# 3_-PowerIN_Page.net
KiCad netlist of a schematic drawn in Altium Designer
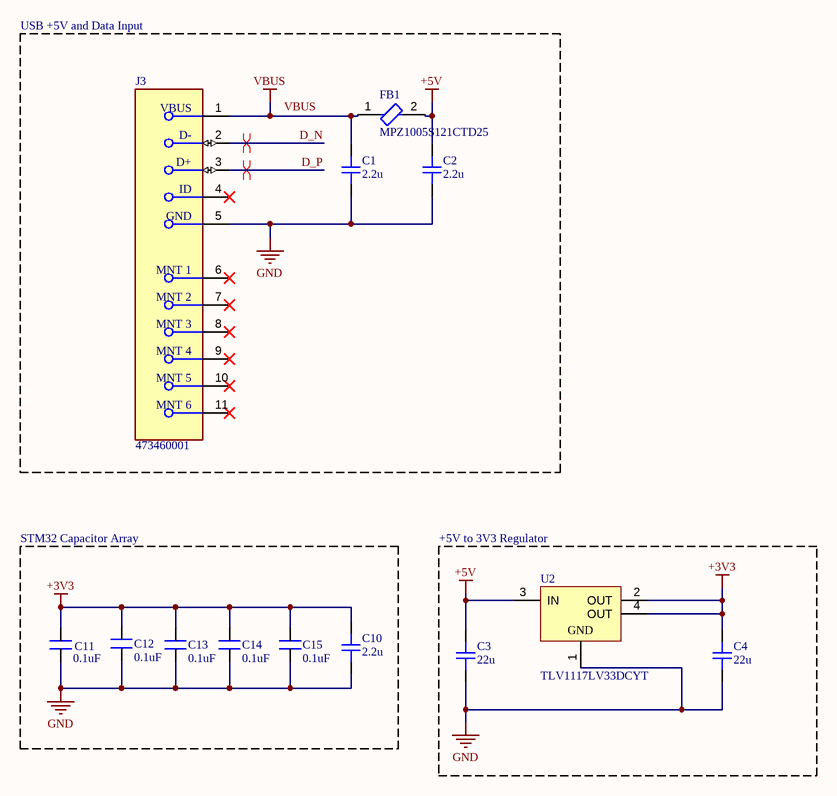
[diagram p0: [3]-PowerIN_Page.SchDoc]

(export (version "E")
  (design (tool "Eeschema 10.0.6"))
  (components
    (comp (ref "C1")
      (value "2.2u")
      (footprint "CAP_0603")
      (description "Capacitor SMD 0603")
      (libsource (lib "Schematic-Lib-PhilsLab") (part "CAP_0603"))
    )
    (comp (ref "C2")
      (value "2.2u")
      (footprint "CAP_0603")
      (description "Capacitor SMD 0603")
      (libsource (lib "Schematic-Lib-PhilsLab") (part "CAP_0603"))
    )
    (comp (ref "C3")
      (value "22u")
      (footprint "CAP_0805")
      (description "Capacitor SMD 0805")
      (libsource (lib "Schematic-Lib-PhilsLab") (part "CAP_0805"))
    )
    (comp (ref "C4")
      (value "22u")
      (footprint "CAP_0805")
      (description "Capacitor SMD 0805")
      (libsource (lib "Schematic-Lib-PhilsLab") (part "CAP_0805"))
    )
    (comp (ref "C10")
      (value "2.2u")
      (footprint "CAP_0603")
      (description "Capacitor SMD 0603")
      (libsource (lib "Schematic-Lib-PhilsLab") (part "CAP_0603"))
    )
    (comp (ref "C11")
      (value "0.1uF")
      (footprint "CAP_0805")
      (description "0.1µF ±5% 50V Ceramic Capacitor X7R 0805 (2012 Metric)")
      (fields
        (field (name "MANUFACTURER") "KEMET")
        (field (name "MANUFACTURING PART NUMBER") "C0805C104J5RACTU")
      )
      (libsource (lib "STM_SCH_LIB") (part "CAP_0.1uF-50V-5%-0805"))
    )
    (comp (ref "C12")
      (value "0.1uF")
      (footprint "CAP_0805")
      (description "0.1µF ±5% 50V Ceramic Capacitor X7R 0805 (2012 Metric)")
      (fields
        (field (name "MANUFACTURER") "KEMET")
        (field (name "MANUFACTURING PART NUMBER") "C0805C104J5RACTU")
      )
      (libsource (lib "STM_SCH_LIB") (part "CAP_0.1uF-50V-5%-0805"))
    )
    (comp (ref "C13")
      (value "0.1uF")
      (footprint "CAP_0805")
      (description "0.1µF ±5% 50V Ceramic Capacitor X7R 0805 (2012 Metric)")
      (fields
        (field (name "MANUFACTURER") "KEMET")
        (field (name "MANUFACTURING PART NUMBER") "C0805C104J5RACTU")
      )
      (libsource (lib "STM_SCH_LIB") (part "CAP_0.1uF-50V-5%-0805"))
    )
    (comp (ref "C14")
      (value "0.1uF")
      (footprint "CAP_0805")
      (description "0.1µF ±5% 50V Ceramic Capacitor X7R 0805 (2012 Metric)")
      (fields
        (field (name "MANUFACTURER") "KEMET")
        (field (name "MANUFACTURING PART NUMBER") "C0805C104J5RACTU")
      )
      (libsource (lib "STM_SCH_LIB") (part "CAP_0.1uF-50V-5%-0805"))
    )
    (comp (ref "C15")
      (value "0.1uF")
      (footprint "CAP_0805")
      (description "0.1µF ±5% 50V Ceramic Capacitor X7R 0805 (2012 Metric)")
      (fields
        (field (name "MANUFACTURER") "KEMET")
        (field (name "MANUFACTURING PART NUMBER") "C0805C104J5RACTU")
      )
      (libsource (lib "STM_SCH_LIB") (part "CAP_0.1uF-50V-5%-0805"))
    )
    (comp (ref "FB1")
      (value "MPZ1005S121CTD25")
      (footprint "FP-MPZ1005-IPC_C")
      (description "Power line Ferrite Bead 120Ω @ 100MHz 1.2A DCR 0.09Ω AEC-Q200 SMD 0402")
      (fields (field (name "TOLERANCE") "25%"))
      (libsource (lib "Altium Content Vault") (part "5f30dd21d616792df468990f7003faa"))
    )
    (comp (ref "J3")
      (value "473460001")
      (footprint "FP-473460001-MFG")
      (description "CONN RCPT USB2.0 MICRO B SMD R/A")
      (fields
        (field (name "OCTOPART") "https://octopart.com/47346-0001-molex-7164928")
        (field (name "MANUFACTURER") "Molex")
      )
      (libsource (lib "Altium Content Vault") (part "53ae1f1d9b557310b43ca686e5bb76a"))
    )
    (comp (ref "U2")
      (value "TLV1117LV33DCYT")
      (footprint "DCY0004A_M")
      (fields (field (name "MANUFACTURER") "Texas Instruments"))
      (libsource (lib "Altium Content Vault") (part "TI-TLV1117LV33DCY4"))
    )
  )
  (nets
    (net (code "1") (name "+3V3") (class "Default")
      (node (ref "C10") (pin "2") (pinfunction "2_2") (pintype "passive"))
      (node (ref "C11") (pin "2") (pinfunction "2_2") (pintype "passive"))
      (node (ref "C12") (pin "2") (pinfunction "2_2") (pintype "passive"))
      (node (ref "C13") (pin "2") (pinfunction "2_2") (pintype "passive"))
      (node (ref "C14") (pin "2") (pinfunction "2_2") (pintype "passive"))
      (node (ref "C15") (pin "2") (pinfunction "2_2") (pintype "passive"))
      (node (ref "C4") (pin "2") (pinfunction "2_2") (pintype "passive"))
      (node (ref "U2") (pin "2") (pinfunction "OUT_2") (pintype "power_in"))
      (node (ref "U2") (pin "4") (pinfunction "OUT_4") (pintype "power_in"))
    )
    (net (code "2") (name "+5V") (class "Default")
      (node (ref "C2") (pin "2") (pinfunction "2_2") (pintype "passive"))
      (node (ref "C3") (pin "2") (pinfunction "2_2") (pintype "passive"))
      (node (ref "FB1") (pin "2") (pinfunction "2_2") (pintype "passive"))
      (node (ref "U2") (pin "3") (pinfunction "IN_3") (pintype "power_in"))
    )
    (net (code "3") (name "/D_N") (class "Default")
      (node (ref "J3") (pin "2") (pinfunction "D-_2") (pintype "bidirectional"))
    )
    (net (code "4") (name "/D_P") (class "Default")
      (node (ref "J3") (pin "3") (pinfunction "D+_3") (pintype "bidirectional"))
    )
    (net (code "5") (name "GND") (class "Default")
      (node (ref "C1") (pin "1") (pinfunction "1_1") (pintype "passive"))
      (node (ref "C10") (pin "1") (pinfunction "1_1") (pintype "passive"))
      (node (ref "C11") (pin "1") (pinfunction "1_1") (pintype "passive"))
      (node (ref "C12") (pin "1") (pinfunction "1_1") (pintype "passive"))
      (node (ref "C13") (pin "1") (pinfunction "1_1") (pintype "passive"))
      (node (ref "C14") (pin "1") (pinfunction "1_1") (pintype "passive"))
      (node (ref "C15") (pin "1") (pinfunction "1_1") (pintype "passive"))
      (node (ref "C2") (pin "1") (pinfunction "1_1") (pintype "passive"))
      (node (ref "C3") (pin "1") (pinfunction "1_1") (pintype "passive"))
      (node (ref "C4") (pin "1") (pinfunction "1_1") (pintype "passive"))
      (node (ref "J3") (pin "5") (pinfunction "GND_5") (pintype "power_in"))
      (node (ref "U2") (pin "1") (pinfunction "GND_1") (pintype "power_in"))
    )
    (net (code "6") (name "VBUS") (class "Default")
      (node (ref "C1") (pin "2") (pinfunction "2_2") (pintype "passive"))
      (node (ref "FB1") (pin "1") (pinfunction "1_1") (pintype "passive"))
      (node (ref "J3") (pin "1") (pinfunction "VBUS_1") (pintype "power_in"))
    )
    (net (code "7") (name "unconnected-(J3-ID-Pad4)") (class "Default")
      (node (ref "J3") (pin "4") (pinfunction "ID_4") (pintype "passive+no_connect"))
    )
    (net (code "8") (name "unconnected-(J3-MNT_1-Pad6)") (class "Default")
      (node (ref "J3") (pin "6") (pinfunction "MNT_1_6") (pintype "passive+no_connect"))
    )
    (net (code "9") (name "unconnected-(J3-MNT_2-Pad7)") (class "Default")
      (node (ref "J3") (pin "7") (pinfunction "MNT_2_7") (pintype "passive+no_connect"))
    )
    (net (code "10") (name "unconnected-(J3-MNT_3-Pad8)") (class "Default")
      (node (ref "J3") (pin "8") (pinfunction "MNT_3_8") (pintype "passive+no_connect"))
    )
    (net (code "11") (name "unconnected-(J3-MNT_4-Pad9)") (class "Default")
      (node (ref "J3") (pin "9") (pinfunction "MNT_4_9") (pintype "passive+no_connect"))
    )
    (net (code "12") (name "unconnected-(J3-MNT_5-Pad10)") (class "Default")
      (node (ref "J3") (pin "10") (pinfunction "MNT_5_10") (pintype "passive+no_connect"))
    )
    (net (code "13") (name "unconnected-(J3-MNT_6-Pad11)") (class "Default")
      (node (ref "J3") (pin "11") (pinfunction "MNT_6_11") (pintype "passive+no_connect"))
    )
  )
)
